# EasyEDA_schematic.net
KiCad netlist of a schematic drawn in EasyEDA
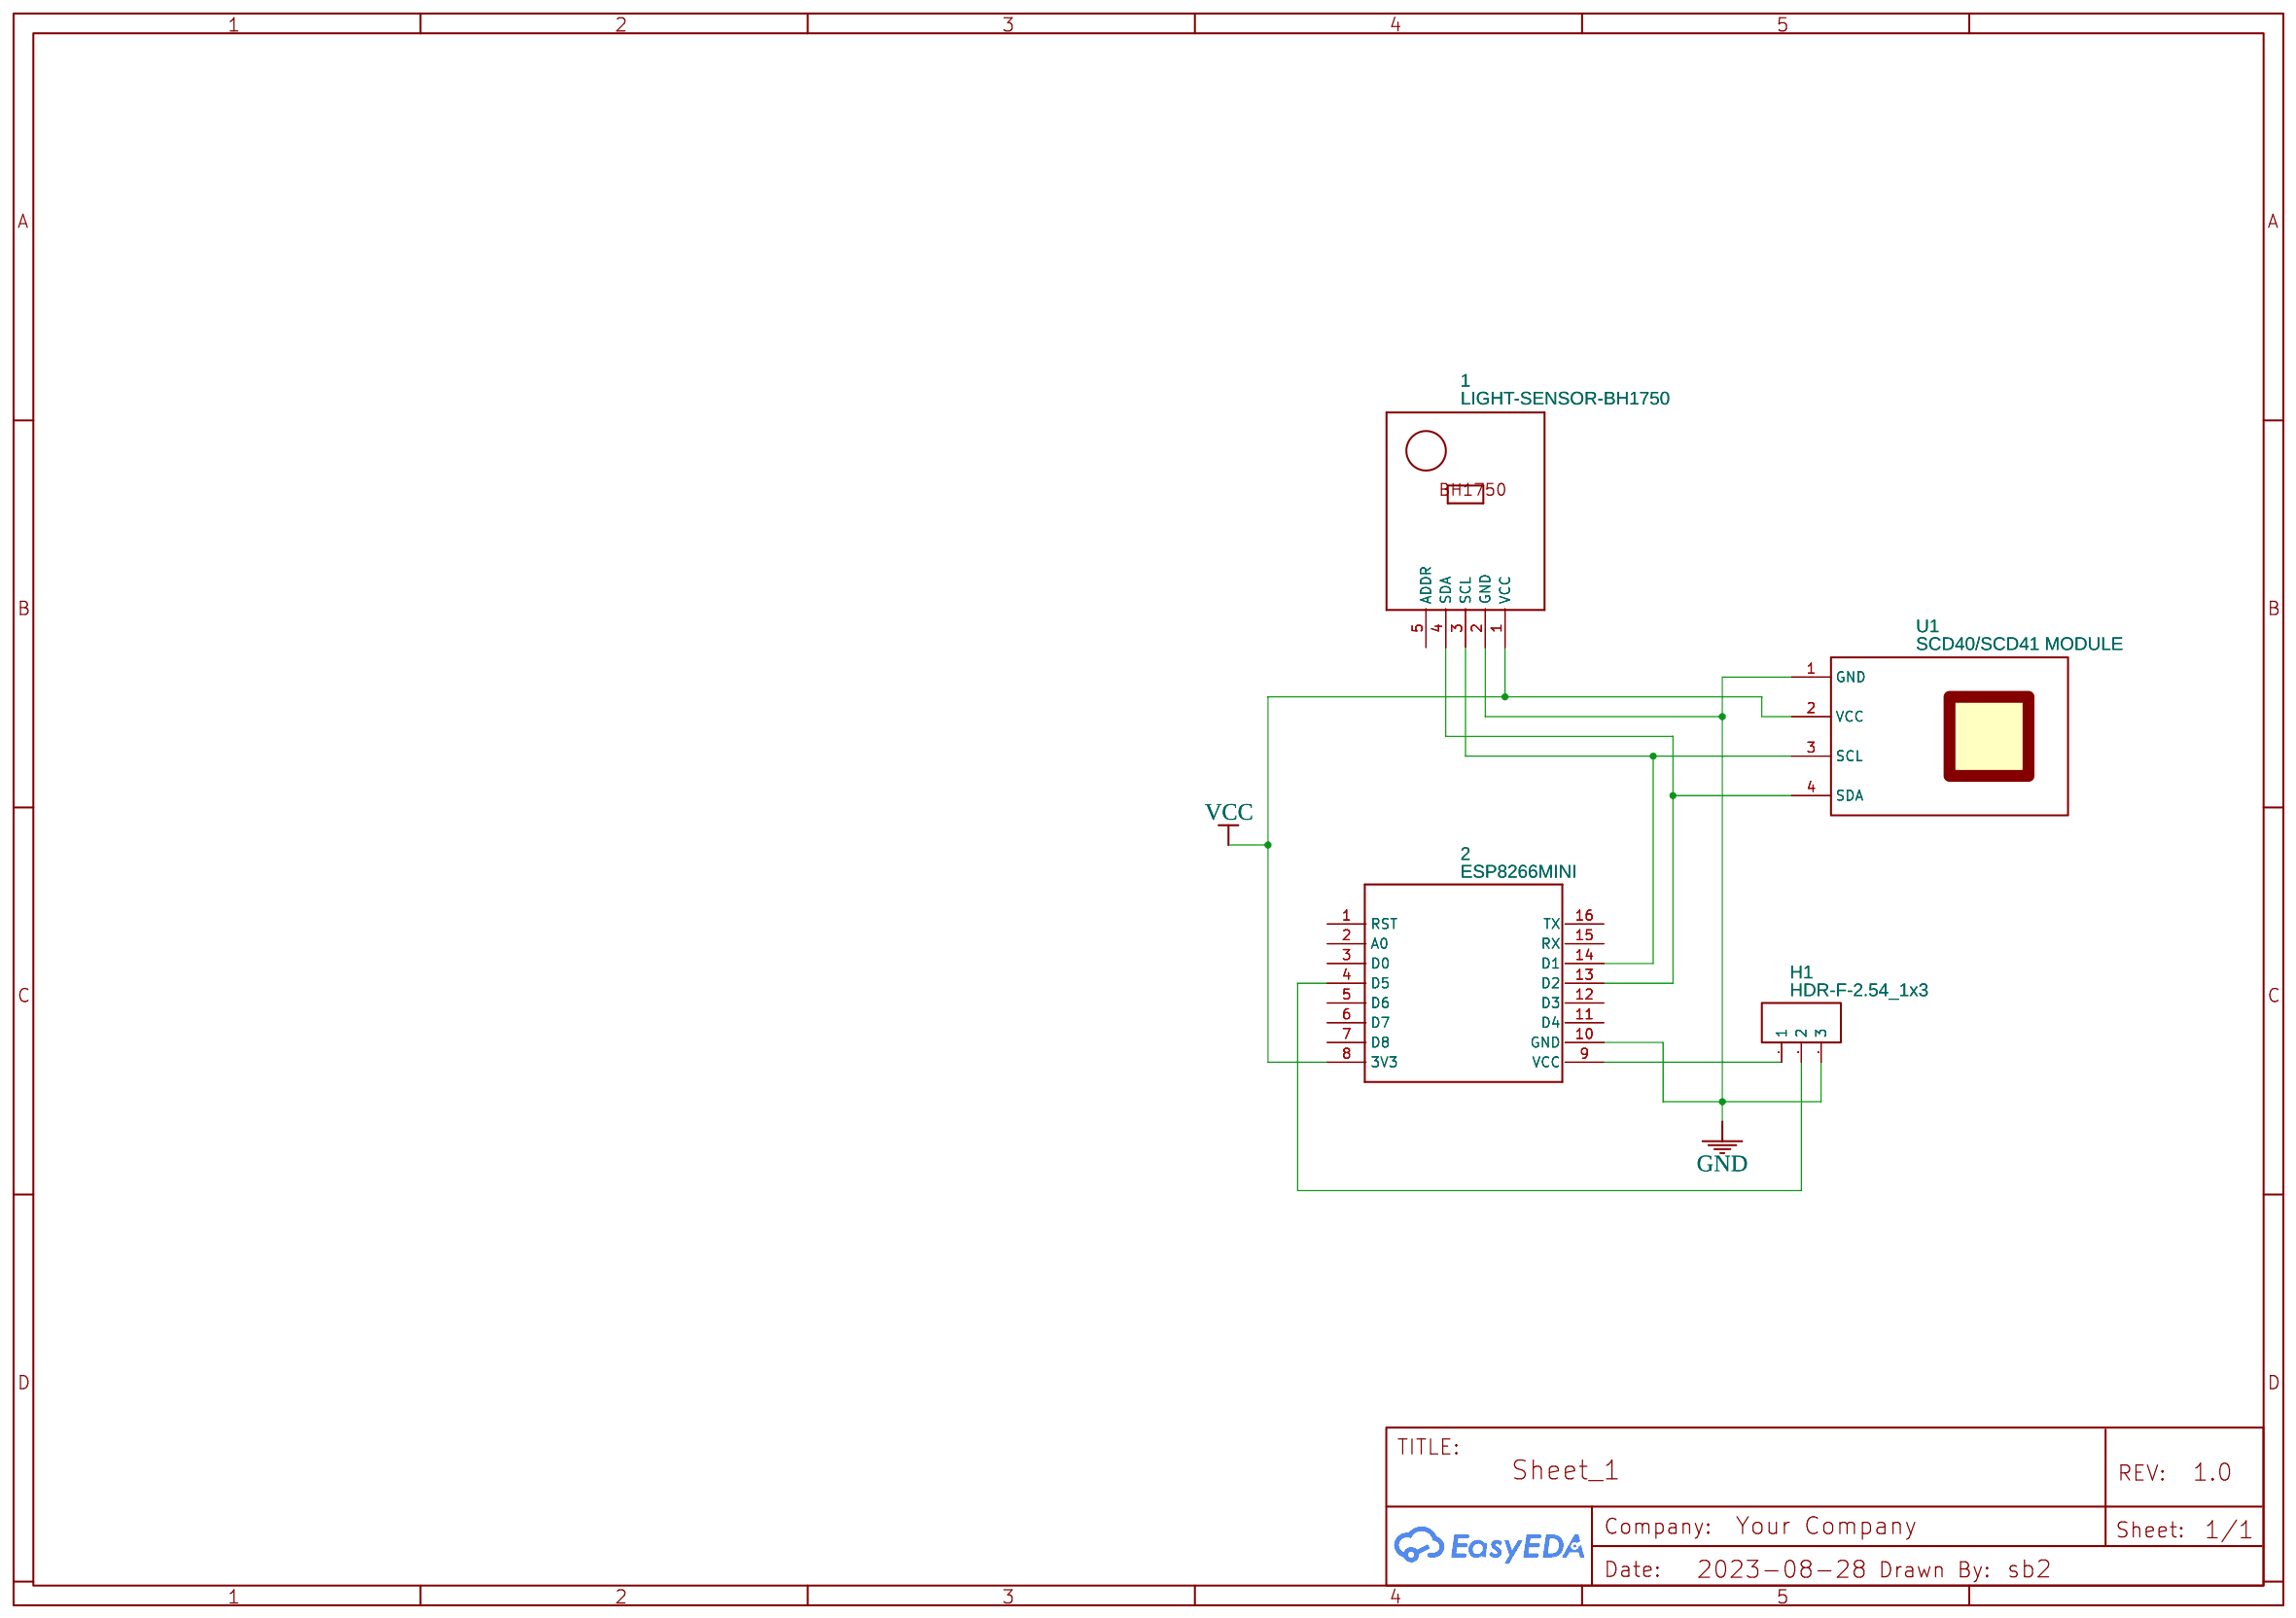
[diagram p0: schematic sheet]

(export (version "E")
  (design (tool "Eeschema 10.0.6"))
  (components
    (comp (ref "1") (value "LIGHT-SENSOR-BH1750") (libsource (lib "") (part "LIGHT-SENSOR-BH1750")))
    (comp (ref "2") (value "ESP8266MINI") (libsource (lib "") (part "ESP8266MINI")))
    (comp (ref "H1") (value "HDR-F-2.54_1x3") (libsource (lib "") (part "HDR-F-2.54_1x3")))
    (comp (ref "U1") (value "SCD40/SCD41 MODULE") (libsource (lib "") (part "SCD40/SCD41 MODULE")))
  )
  (nets
    (net (code "1") (name "GND") (class "Default")
      (node (ref "1") (pin "2") (pinfunction "GND_2") (pintype "bidirectional"))
      (node (ref "2") (pin "10") (pinfunction "GND_10") (pintype "bidirectional"))
      (node (ref "H1") (pin "3") (pinfunction "3_3") (pintype "input"))
      (node (ref "U1") (pin "1") (pinfunction "GND_1") (pintype "unspecified"))
    )
    (net (code "2") (name "Net-(1-SCL)") (class "Default")
      (node (ref "1") (pin "3") (pinfunction "SCL_3") (pintype "bidirectional"))
      (node (ref "2") (pin "14") (pinfunction "D1_14") (pintype "bidirectional"))
      (node (ref "U1") (pin "3") (pinfunction "SCL_3") (pintype "unspecified"))
    )
    (net (code "3") (name "Net-(1-SDA)") (class "Default")
      (node (ref "1") (pin "4") (pinfunction "SDA_4") (pintype "bidirectional"))
      (node (ref "2") (pin "13") (pinfunction "D2_13") (pintype "bidirectional"))
      (node (ref "U1") (pin "4") (pinfunction "SDA_4") (pintype "unspecified"))
    )
    (net (code "4") (name "Net-(2-D5)") (class "Default")
      (node (ref "2") (pin "4") (pinfunction "D5_4") (pintype "bidirectional"))
      (node (ref "H1") (pin "2") (pinfunction "2_2") (pintype "input"))
    )
    (net (code "5") (name "Net-(2-VCC)") (class "Default")
      (node (ref "2") (pin "9") (pinfunction "VCC_9") (pintype "bidirectional"))
      (node (ref "H1") (pin "1") (pinfunction "1_1") (pintype "input"))
    )
    (net (code "6") (name "VCC") (class "Default")
      (node (ref "1") (pin "1") (pinfunction "VCC_1") (pintype "bidirectional"))
      (node (ref "2") (pin "8") (pinfunction "3V3_8") (pintype "bidirectional"))
      (node (ref "U1") (pin "2") (pinfunction "VCC_2") (pintype "unspecified"))
    )
    (net (code "7") (name "unconnected-(1-ADDR-Pad5)") (class "Default")
      (node (ref "1") (pin "5") (pinfunction "ADDR_5") (pintype "bidirectional"))
    )
    (net (code "8") (name "unconnected-(2-A0-Pad2)") (class "Default")
      (node (ref "2") (pin "2") (pinfunction "A0_2") (pintype "bidirectional"))
    )
    (net (code "9") (name "unconnected-(2-D0-Pad3)") (class "Default")
      (node (ref "2") (pin "3") (pinfunction "D0_3") (pintype "bidirectional"))
    )
    (net (code "10") (name "unconnected-(2-D3-Pad12)") (class "Default")
      (node (ref "2") (pin "12") (pinfunction "D3_12") (pintype "bidirectional"))
    )
    (net (code "11") (name "unconnected-(2-D4-Pad11)") (class "Default")
      (node (ref "2") (pin "11") (pinfunction "D4_11") (pintype "bidirectional"))
    )
    (net (code "12") (name "unconnected-(2-D6-Pad5)") (class "Default")
      (node (ref "2") (pin "5") (pinfunction "D6_5") (pintype "bidirectional"))
    )
    (net (code "13") (name "unconnected-(2-D7-Pad6)") (class "Default")
      (node (ref "2") (pin "6") (pinfunction "D7_6") (pintype "bidirectional"))
    )
    (net (code "14") (name "unconnected-(2-D8-Pad7)") (class "Default")
      (node (ref "2") (pin "7") (pinfunction "D8_7") (pintype "bidirectional"))
    )
    (net (code "15") (name "unconnected-(2-RST-Pad1)") (class "Default")
      (node (ref "2") (pin "1") (pinfunction "RST_1") (pintype "bidirectional"))
    )
    (net (code "16") (name "unconnected-(2-RX-Pad15)") (class "Default")
      (node (ref "2") (pin "15") (pinfunction "RX_15") (pintype "bidirectional"))
    )
    (net (code "17") (name "unconnected-(2-TX-Pad16)") (class "Default")
      (node (ref "2") (pin "16") (pinfunction "TX_16") (pintype "bidirectional"))
    )
  )
)
